# Sheet2.net
KiCad netlist of a schematic drawn in Altium Designer
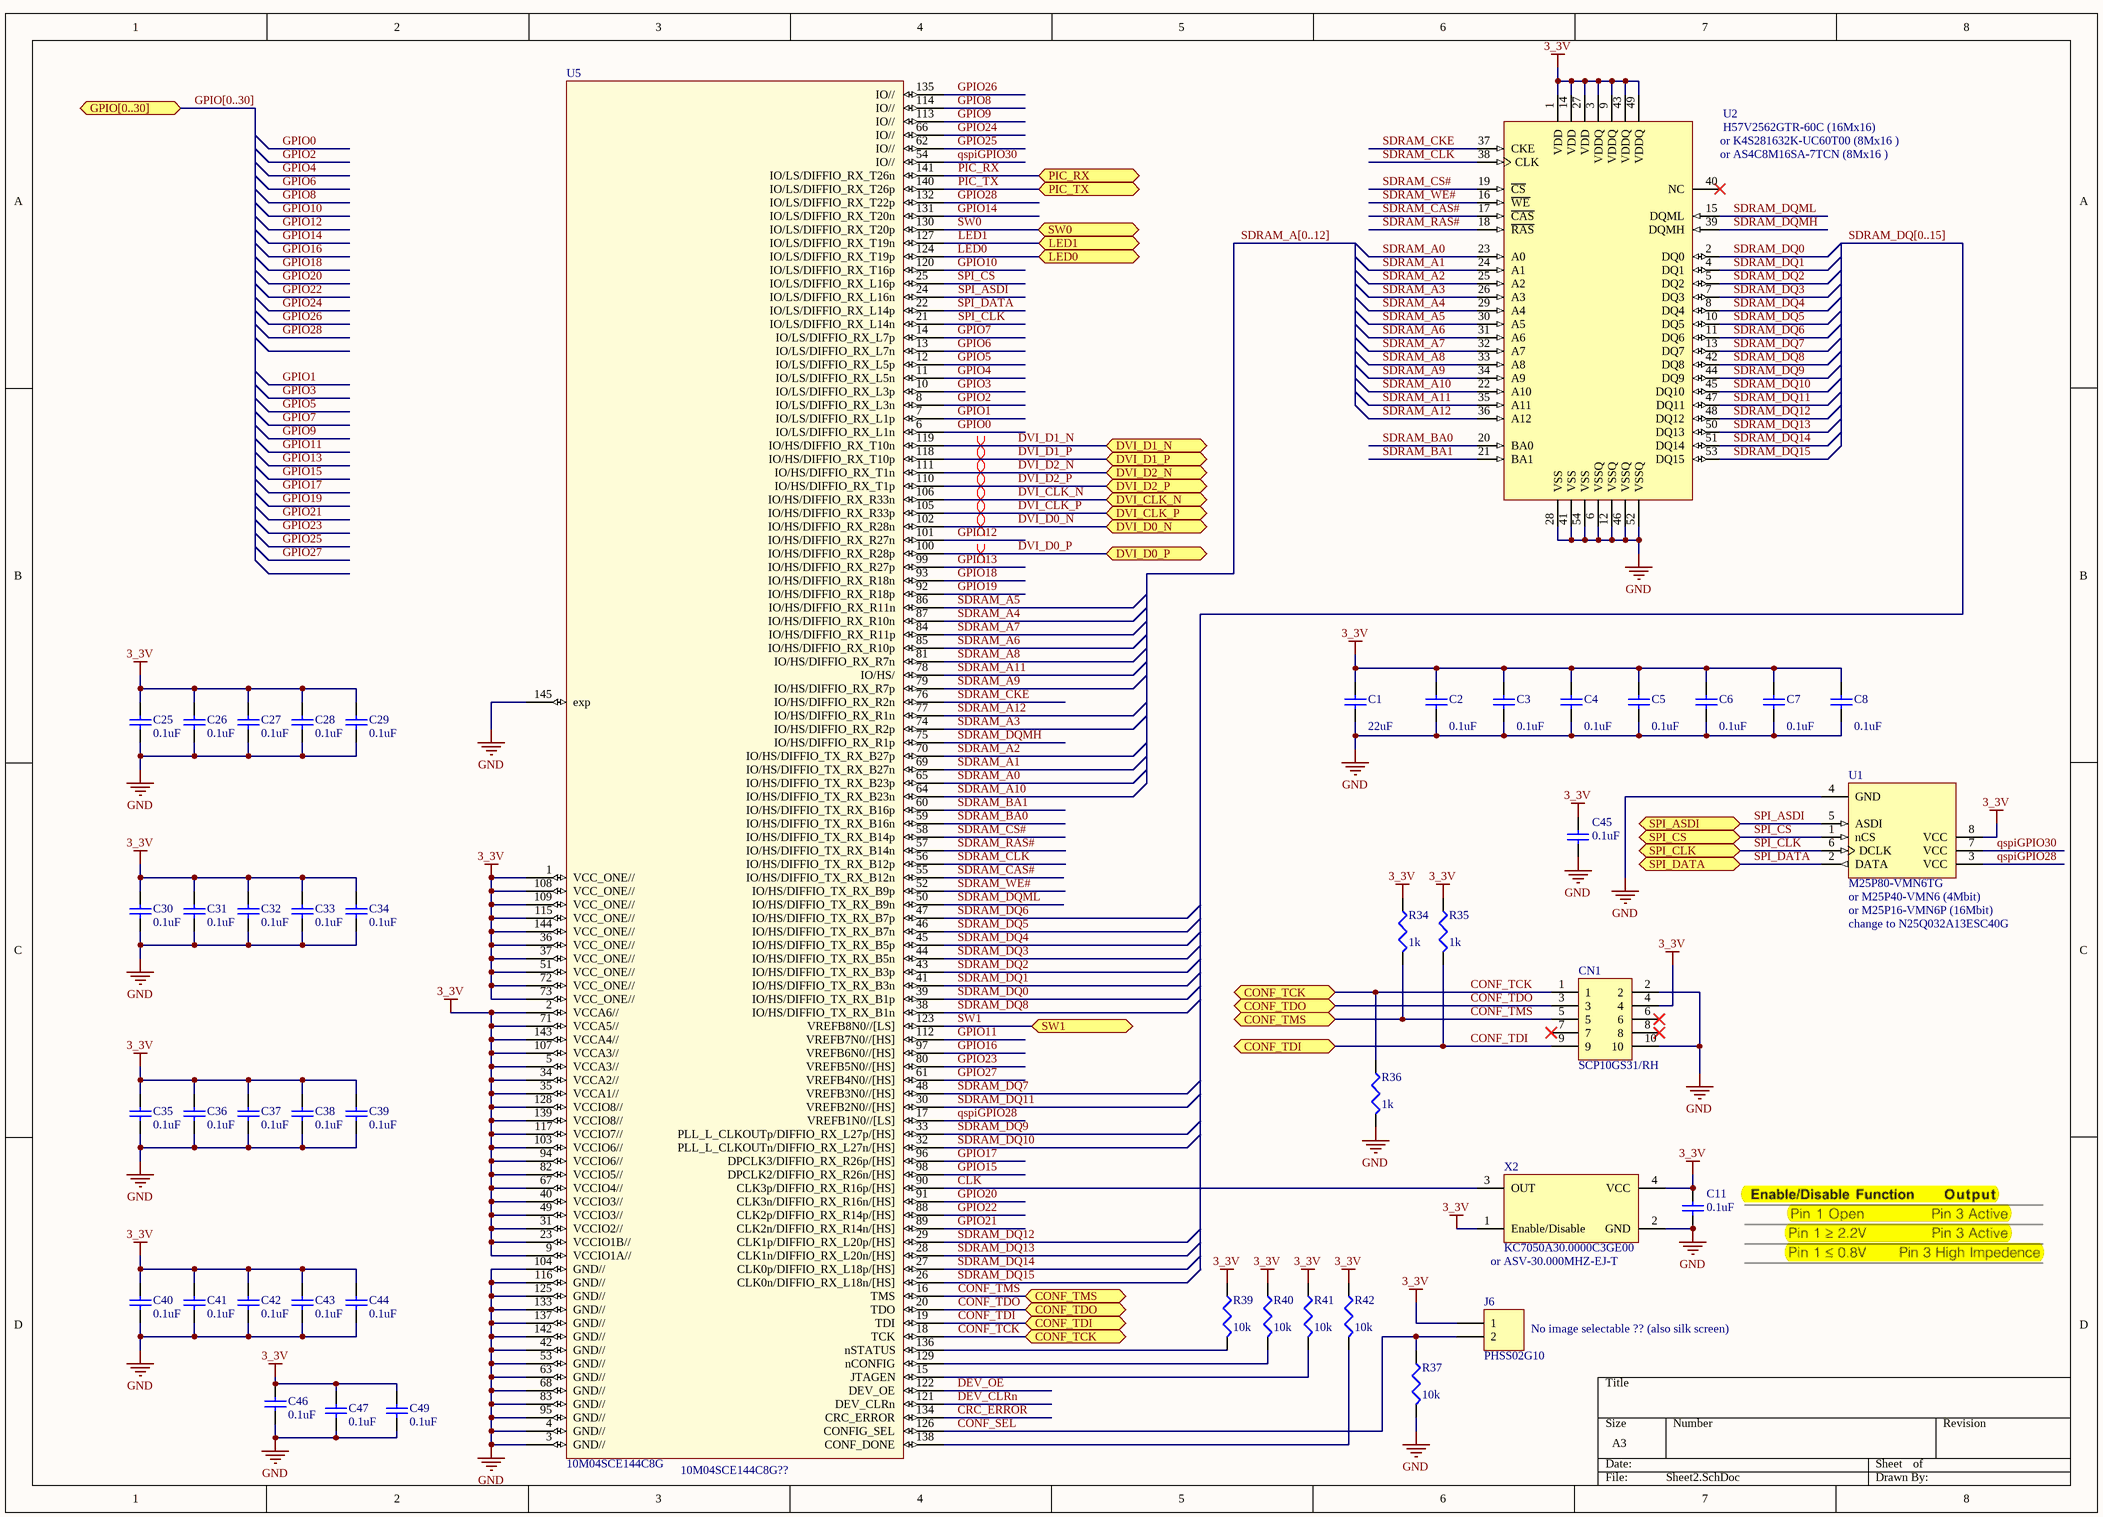
[diagram p0: Sheet2.SchDoc]

(export (version "E")
  (design (tool "Eeschema 10.0.6"))
  (components
    (comp (ref "C1")
      (value "22uF")
      (footprint "PcbLib:CHIP3216")
      (description "Capacitor (Semiconductor SIM Model)")
      (fields (field (name "Comment") "MC1206F226Z100CT") (field (name "PUBLISHER") "Altium Limited"))
      (libsource (lib "Miscellaneous Devices") (part "Cap Semi"))
    )
    (comp (ref "C2")
      (value "0.1uF")
      (footprint "PcbLib:CHIP1608")
      (description "Capacitor (Semiconductor SIM Model)")
      (fields (field (name "Comment") "MC0603B104M160CT") (field (name "PUBLISHER") "Altium Limited"))
      (libsource (lib "Miscellaneous Devices") (part "Cap Semi"))
    )
    (comp (ref "C3")
      (value "0.1uF")
      (footprint "PcbLib:CHIP1608")
      (description "Capacitor (Semiconductor SIM Model)")
      (fields (field (name "Comment") "MC0603B104M160CT") (field (name "PUBLISHER") "Altium Limited"))
      (libsource (lib "Miscellaneous Devices") (part "Cap Semi"))
    )
    (comp (ref "C4")
      (value "0.1uF")
      (footprint "PcbLib:CHIP1608")
      (description "Capacitor (Semiconductor SIM Model)")
      (fields (field (name "Comment") "MC0603B104M160CT") (field (name "PUBLISHER") "Altium Limited"))
      (libsource (lib "Miscellaneous Devices") (part "Cap Semi"))
    )
    (comp (ref "C5")
      (value "0.1uF")
      (footprint "PcbLib:CHIP1608")
      (description "Capacitor (Semiconductor SIM Model)")
      (fields (field (name "Comment") "MC0603B104M160CT") (field (name "PUBLISHER") "Altium Limited"))
      (libsource (lib "Miscellaneous Devices") (part "Cap Semi"))
    )
    (comp (ref "C6")
      (value "0.1uF")
      (footprint "PcbLib:CHIP1608")
      (description "Capacitor (Semiconductor SIM Model)")
      (fields (field (name "Comment") "MC0603B104M160CT") (field (name "PUBLISHER") "Altium Limited"))
      (libsource (lib "Miscellaneous Devices") (part "Cap Semi"))
    )
    (comp (ref "C7")
      (value "0.1uF")
      (footprint "PcbLib:CHIP1608")
      (description "Capacitor (Semiconductor SIM Model)")
      (fields (field (name "Comment") "MC0603B104M160CT") (field (name "PUBLISHER") "Altium Limited"))
      (libsource (lib "Miscellaneous Devices") (part "Cap Semi"))
    )
    (comp (ref "C8")
      (value "0.1uF")
      (footprint "PcbLib:CHIP1608")
      (description "Capacitor (Semiconductor SIM Model)")
      (fields (field (name "Comment") "MC0603B104M160CT") (field (name "PUBLISHER") "Altium Limited"))
      (libsource (lib "Miscellaneous Devices") (part "Cap Semi"))
    )
    (comp (ref "C11")
      (value "0.1uF")
      (footprint "PcbLib:CHIP1608")
      (description "Capacitor (Semiconductor SIM Model)")
      (fields (field (name "Comment") "MC0603B104M160CT") (field (name "PUBLISHER") "Altium Limited"))
      (libsource (lib "Miscellaneous Devices") (part "Cap Semi"))
    )
    (comp (ref "C25")
      (value "0.1uF")
      (footprint "PcbLib:CHIP1608")
      (description "Capacitor (Semiconductor SIM Model)")
      (fields (field (name "Comment") "MC0603B104M160CT") (field (name "PUBLISHER") "Altium Limited"))
      (libsource (lib "Miscellaneous Devices") (part "Cap Semi"))
    )
    (comp (ref "C26")
      (value "0.1uF")
      (footprint "PcbLib:CHIP1608")
      (description "Capacitor (Semiconductor SIM Model)")
      (fields (field (name "Comment") "MC0603B104M160CT") (field (name "PUBLISHER") "Altium Limited"))
      (libsource (lib "Miscellaneous Devices") (part "Cap Semi"))
    )
    (comp (ref "C27")
      (value "0.1uF")
      (footprint "PcbLib:CHIP1608")
      (description "Capacitor (Semiconductor SIM Model)")
      (fields (field (name "Comment") "MC0603B104M160CT") (field (name "PUBLISHER") "Altium Limited"))
      (libsource (lib "Miscellaneous Devices") (part "Cap Semi"))
    )
    (comp (ref "C28")
      (value "0.1uF")
      (footprint "PcbLib:CHIP1608")
      (description "Capacitor (Semiconductor SIM Model)")
      (fields (field (name "Comment") "MC0603B104M160CT") (field (name "PUBLISHER") "Altium Limited"))
      (libsource (lib "Miscellaneous Devices") (part "Cap Semi"))
    )
    (comp (ref "C29")
      (value "0.1uF")
      (footprint "PcbLib:CHIP1608")
      (description "Capacitor (Semiconductor SIM Model)")
      (fields (field (name "Comment") "MC0603B104M160CT") (field (name "PUBLISHER") "Altium Limited"))
      (libsource (lib "Miscellaneous Devices") (part "Cap Semi"))
    )
    (comp (ref "C30")
      (value "0.1uF")
      (footprint "PcbLib:CHIP1608")
      (description "Capacitor (Semiconductor SIM Model)")
      (fields (field (name "Comment") "MC0603B104M160CT") (field (name "PUBLISHER") "Altium Limited"))
      (libsource (lib "Miscellaneous Devices") (part "Cap Semi"))
    )
    (comp (ref "C31")
      (value "0.1uF")
      (footprint "PcbLib:CHIP1608")
      (description "Capacitor (Semiconductor SIM Model)")
      (fields (field (name "Comment") "MC0603B104M160CT") (field (name "PUBLISHER") "Altium Limited"))
      (libsource (lib "Miscellaneous Devices") (part "Cap Semi"))
    )
    (comp (ref "C32")
      (value "0.1uF")
      (footprint "PcbLib:CHIP1608")
      (description "Capacitor (Semiconductor SIM Model)")
      (fields (field (name "Comment") "MC0603B104M160CT") (field (name "PUBLISHER") "Altium Limited"))
      (libsource (lib "Miscellaneous Devices") (part "Cap Semi"))
    )
    (comp (ref "C33")
      (value "0.1uF")
      (footprint "PcbLib:CHIP1608")
      (description "Capacitor (Semiconductor SIM Model)")
      (fields (field (name "Comment") "MC0603B104M160CT") (field (name "PUBLISHER") "Altium Limited"))
      (libsource (lib "Miscellaneous Devices") (part "Cap Semi"))
    )
    (comp (ref "C34")
      (value "0.1uF")
      (footprint "PcbLib:CHIP1608")
      (description "Capacitor (Semiconductor SIM Model)")
      (fields (field (name "Comment") "MC0603B104M160CT") (field (name "PUBLISHER") "Altium Limited"))
      (libsource (lib "Miscellaneous Devices") (part "Cap Semi"))
    )
    (comp (ref "C35")
      (value "0.1uF")
      (footprint "PcbLib:CHIP1608")
      (description "Capacitor (Semiconductor SIM Model)")
      (fields (field (name "Comment") "MC0603B104M160CT") (field (name "PUBLISHER") "Altium Limited"))
      (libsource (lib "Miscellaneous Devices") (part "Cap Semi"))
    )
    (comp (ref "C36")
      (value "0.1uF")
      (footprint "PcbLib:CHIP1608")
      (description "Capacitor (Semiconductor SIM Model)")
      (fields (field (name "Comment") "MC0603B104M160CT") (field (name "PUBLISHER") "Altium Limited"))
      (libsource (lib "Miscellaneous Devices") (part "Cap Semi"))
    )
    (comp (ref "C37")
      (value "0.1uF")
      (footprint "PcbLib:CHIP1608")
      (description "Capacitor (Semiconductor SIM Model)")
      (fields (field (name "Comment") "MC0603B104M160CT") (field (name "PUBLISHER") "Altium Limited"))
      (libsource (lib "Miscellaneous Devices") (part "Cap Semi"))
    )
    (comp (ref "C38")
      (value "0.1uF")
      (footprint "PcbLib:CHIP1608")
      (description "Capacitor (Semiconductor SIM Model)")
      (fields (field (name "Comment") "MC0603B104M160CT") (field (name "PUBLISHER") "Altium Limited"))
      (libsource (lib "Miscellaneous Devices") (part "Cap Semi"))
    )
    (comp (ref "C39")
      (value "0.1uF")
      (footprint "PcbLib:CHIP1608")
      (description "Capacitor (Semiconductor SIM Model)")
      (fields (field (name "Comment") "MC0603B104M160CT") (field (name "PUBLISHER") "Altium Limited"))
      (libsource (lib "Miscellaneous Devices") (part "Cap Semi"))
    )
    (comp (ref "C40")
      (value "0.1uF")
      (footprint "PcbLib:CHIP1608")
      (description "Capacitor (Semiconductor SIM Model)")
      (fields (field (name "Comment") "MC0603B104M160CT") (field (name "PUBLISHER") "Altium Limited"))
      (libsource (lib "Miscellaneous Devices") (part "Cap Semi"))
    )
    (comp (ref "C41")
      (value "0.1uF")
      (footprint "PcbLib:CHIP1608")
      (description "Capacitor (Semiconductor SIM Model)")
      (fields (field (name "Comment") "MC0603B104M160CT") (field (name "PUBLISHER") "Altium Limited"))
      (libsource (lib "Miscellaneous Devices") (part "Cap Semi"))
    )
    (comp (ref "C42")
      (value "0.1uF")
      (footprint "PcbLib:CHIP1608")
      (description "Capacitor (Semiconductor SIM Model)")
      (fields (field (name "Comment") "MC0603B104M160CT") (field (name "PUBLISHER") "Altium Limited"))
      (libsource (lib "Miscellaneous Devices") (part "Cap Semi"))
    )
    (comp (ref "C43")
      (value "0.1uF")
      (footprint "PcbLib:CHIP1608")
      (description "Capacitor (Semiconductor SIM Model)")
      (fields (field (name "Comment") "MC0603B104M160CT") (field (name "PUBLISHER") "Altium Limited"))
      (libsource (lib "Miscellaneous Devices") (part "Cap Semi"))
    )
    (comp (ref "C44")
      (value "0.1uF")
      (footprint "PcbLib:CHIP1608")
      (description "Capacitor (Semiconductor SIM Model)")
      (fields (field (name "Comment") "MC0603B104M160CT") (field (name "PUBLISHER") "Altium Limited"))
      (libsource (lib "Miscellaneous Devices") (part "Cap Semi"))
    )
    (comp (ref "C45")
      (value "0.1uF")
      (footprint "PcbLib:CHIP1608")
      (description "Capacitor (Semiconductor SIM Model)")
      (fields (field (name "Comment") "MC0603B104M160CT") (field (name "PUBLISHER") "Altium Limited"))
      (libsource (lib "Miscellaneous Devices") (part "Cap Semi"))
    )
    (comp (ref "C46")
      (value "0.1uF")
      (footprint "PcbLib:CHIP1608")
      (description "Capacitor (Semiconductor SIM Model)")
      (fields (field (name "Comment") "MC0603B104M160CT") (field (name "PUBLISHER") "Altium Limited"))
      (libsource (lib "Miscellaneous Devices") (part "Cap Semi"))
    )
    (comp (ref "C47")
      (value "0.1uF")
      (footprint "PcbLib:CHIP1608")
      (description "Capacitor (Semiconductor SIM Model)")
      (fields (field (name "Comment") "MC0603B104M160CT") (field (name "PUBLISHER") "Altium Limited"))
      (libsource (lib "Miscellaneous Devices") (part "Cap Semi"))
    )
    (comp (ref "C49")
      (value "0.1uF")
      (footprint "PcbLib:CHIP1608")
      (description "Capacitor (Semiconductor SIM Model)")
      (fields (field (name "Comment") "MC0603B104M160CT") (field (name "PUBLISHER") "Altium Limited"))
      (libsource (lib "Miscellaneous Devices") (part "Cap Semi"))
    )
    (comp (ref "CN1")
      (value "SCP10GS31/RH")
      (footprint "SCP10GS31/RH")
      (description "GTK")
      (libsource (lib "Schlib1") (part "SCP10GS31/RH"))
    )
    (comp (ref "J6")
      (value "PHSS02G10")
      (footprint "PcbLib:HDR1X2")
      (description "Header, 2-Pin")
      (fields (field (name "PUBLISHER") "Altium Limited"))
      (libsource (lib "Miscellaneous Connectors") (part "Header 2"))
    )
    (comp (ref "R34")
      (value "1k")
      (footprint "PcbLib:CHIP1608")
      (description "Resistor")
      (fields (field (name "Comment") "MCMR06X1001FTL") (field (name "PUBLISHER") "Altium Limited"))
      (libsource (lib "Miscellaneous Devices") (part "Res3"))
    )
    (comp (ref "R35")
      (value "1k")
      (footprint "PcbLib:CHIP1608")
      (description "Resistor")
      (fields (field (name "Comment") "MCMR06X1001FTL") (field (name "PUBLISHER") "Altium Limited"))
      (libsource (lib "Miscellaneous Devices") (part "Res3"))
    )
    (comp (ref "R36")
      (value "1k")
      (footprint "PcbLib:CHIP1608")
      (description "Resistor")
      (fields (field (name "Comment") "MCMR06X1001FTL") (field (name "PUBLISHER") "Altium Limited"))
      (libsource (lib "Miscellaneous Devices") (part "Res3"))
    )
    (comp (ref "R37")
      (value "10k")
      (footprint "PcbLib:CHIP1608")
      (description "Resistor")
      (fields (field (name "Comment") "MCWR06X1002FTL") (field (name "PUBLISHER") "Altium Limited"))
      (libsource (lib "Miscellaneous Devices") (part "Res3"))
    )
    (comp (ref "R39")
      (value "10k")
      (footprint "PcbLib:CHIP1608")
      (description "Resistor")
      (fields (field (name "Comment") "MCWR06X1002FTL") (field (name "PUBLISHER") "Altium Limited"))
      (libsource (lib "Miscellaneous Devices") (part "Res3"))
    )
    (comp (ref "R40")
      (value "10k")
      (footprint "PcbLib:CHIP1608")
      (description "Resistor")
      (fields (field (name "Comment") "MCWR06X1002FTL") (field (name "PUBLISHER") "Altium Limited"))
      (libsource (lib "Miscellaneous Devices") (part "Res3"))
    )
    (comp (ref "R41")
      (value "10k")
      (footprint "PcbLib:CHIP1608")
      (description "Resistor")
      (fields (field (name "Comment") "MCWR06X1002FTL") (field (name "PUBLISHER") "Altium Limited"))
      (libsource (lib "Miscellaneous Devices") (part "Res3"))
    )
    (comp (ref "R42")
      (value "10k")
      (footprint "PcbLib:CHIP1608")
      (description "Resistor")
      (fields (field (name "Comment") "MCWR06X1002FTL") (field (name "PUBLISHER") "Altium Limited"))
      (libsource (lib "Miscellaneous Devices") (part "Res3"))
    )
    (comp (ref "U1")
      (value "M25P80-VMN6TG")
      (footprint "PcbLib:SOIC8_L")
      (fields (field (name "PUBLISHER") "Altium Limited"))
      (libsource (lib "Altera EPCS Configuration Device") (part "EPCS1SI8"))
    )
    (comp (ref "U2")
      (value "H57V2562GTR-60C (16Mx16)")
      (footprint "TSOP2-54_M")
      (description "MICRON")
      (fields (field (name "PUBLISHER") "Altium Limited"))
      (libsource (lib "Micron Memory Dynamic RAM") (part "MT48LC16M16A2TG-75"))
    )
    (comp (ref "U5")
      (value "10M04SCE144C8G")
      (footprint "PcbLib:TEST2")
      (description "MAX10")
      (libsource (lib "Schlib") (part "MAX10"))
    )
    (comp (ref "X2")
      (value "KC7050A30.0000C3GE00")
      (footprint "CWX823-50.0M")
      (description "CONNOR-WINFIELD")
      (libsource (lib "Schlib1") (part "CWX823-50.0M"))
    )
  )
  (nets
    (net (code "3") (name "/CLK") (class "Default")
      (node (ref "U5") (pin "90") (pinfunction "CLK3p/DIFFIO_RX_R16p/[HS]_90") (pintype "bidirectional"))
      (node (ref "X2") (pin "3") (pinfunction "OUT_3") (pintype "passive"))
    )
    (net (code "4") (name "/CONF_SEL") (class "Default")
      (node (ref "J6") (pin "2") (pinfunction "2_2") (pintype "passive"))
      (node (ref "R37") (pin "1") (pinfunction "1_1") (pintype "passive"))
      (node (ref "U5") (pin "126") (pinfunction "CONFIG_SEL_126") (pintype "bidirectional"))
    )
    (net (code "5") (name "/CONF_TCK") (class "Default")
      (node (ref "CN1") (pin "1") (pinfunction "1_1") (pintype "passive"))
      (node (ref "R36") (pin "1") (pinfunction "1_1") (pintype "passive"))
      (node (ref "U5") (pin "18") (pinfunction "TCK_18") (pintype "bidirectional"))
    )
    (net (code "6") (name "/CONF_TDI") (class "Default")
      (node (ref "CN1") (pin "9") (pinfunction "9_9") (pintype "passive"))
      (node (ref "R35") (pin "2") (pinfunction "2_2") (pintype "passive"))
      (node (ref "U5") (pin "19") (pinfunction "TDI_19") (pintype "bidirectional"))
    )
    (net (code "7") (name "/CONF_TDO") (class "Default")
      (node (ref "CN1") (pin "3") (pinfunction "3_3") (pintype "passive"))
      (node (ref "U5") (pin "20") (pinfunction "TDO_20") (pintype "bidirectional"))
    )
    (net (code "8") (name "/CONF_TMS") (class "Default")
      (node (ref "CN1") (pin "5") (pinfunction "5_5") (pintype "passive"))
      (node (ref "R34") (pin "2") (pinfunction "2_2") (pintype "passive"))
      (node (ref "U5") (pin "16") (pinfunction "TMS_16") (pintype "bidirectional"))
    )
    (net (code "9") (name "/CRC_ERROR") (class "Default")
      (node (ref "U5") (pin "134") (pinfunction "CRC_ERROR_134") (pintype "bidirectional"))
    )
    (net (code "10") (name "/DEV_CLRn") (class "Default")
      (node (ref "U5") (pin "121") (pinfunction "DEV_CLRn_121") (pintype "bidirectional"))
    )
    (net (code "11") (name "/DEV_OE") (class "Default")
      (node (ref "U5") (pin "122") (pinfunction "DEV_OE_122") (pintype "bidirectional"))
    )
    (net (code "12") (name "/DVI_CLK_N") (class "Default")
      (node (ref "U5") (pin "106") (pinfunction "IO/HS/DIFFIO_RX_R33n_106") (pintype "bidirectional"))
    )
    (net (code "13") (name "/DVI_CLK_P") (class "Default")
      (node (ref "U5") (pin "105") (pinfunction "IO/HS/DIFFIO_RX_R33p_105") (pintype "bidirectional"))
    )
    (net (code "14") (name "/DVI_D0_N") (class "Default")
      (node (ref "U5") (pin "102") (pinfunction "IO/HS/DIFFIO_RX_R28n_102") (pintype "bidirectional"))
    )
    (net (code "15") (name "/DVI_D0_P") (class "Default")
      (node (ref "U5") (pin "100") (pinfunction "IO/HS/DIFFIO_RX_R28p_100") (pintype "bidirectional"))
    )
    (net (code "16") (name "/DVI_D1_N") (class "Default")
      (node (ref "U5") (pin "119") (pinfunction "IO/HS/DIFFIO_RX_T10n_119") (pintype "bidirectional"))
    )
    (net (code "17") (name "/DVI_D1_P") (class "Default")
      (node (ref "U5") (pin "118") (pinfunction "IO/HS/DIFFIO_RX_T10p_118") (pintype "bidirectional"))
    )
    (net (code "18") (name "/DVI_D2_N") (class "Default")
      (node (ref "U5") (pin "111") (pinfunction "IO/HS/DIFFIO_RX_T1n_111") (pintype "bidirectional"))
    )
    (net (code "19") (name "/DVI_D2_P") (class "Default")
      (node (ref "U5") (pin "110") (pinfunction "IO/HS/DIFFIO_RX_T1p_110") (pintype "bidirectional"))
    )
    (net (code "20") (name "/GPIO0") (class "Default")
      (node (ref "U5") (pin "6") (pinfunction "IO/LS/DIFFIO_RX_L1n_6") (pintype "bidirectional"))
    )
    (net (code "21") (name "/GPIO1") (class "Default")
      (node (ref "U5") (pin "7") (pinfunction "IO/LS/DIFFIO_RX_L1p_7") (pintype "bidirectional"))
    )
    (net (code "22") (name "/GPIO2") (class "Default")
      (node (ref "U5") (pin "8") (pinfunction "IO/LS/DIFFIO_RX_L3n_8") (pintype "bidirectional"))
    )
    (net (code "23") (name "/GPIO3") (class "Default")
      (node (ref "U5") (pin "10") (pinfunction "IO/LS/DIFFIO_RX_L3p_10") (pintype "bidirectional"))
    )
    (net (code "24") (name "/GPIO4") (class "Default")
      (node (ref "U5") (pin "11") (pinfunction "IO/LS/DIFFIO_RX_L5n_11") (pintype "bidirectional"))
    )
    (net (code "25") (name "/GPIO5") (class "Default")
      (node (ref "U5") (pin "12") (pinfunction "IO/LS/DIFFIO_RX_L5p_12") (pintype "bidirectional"))
    )
    (net (code "26") (name "/GPIO6") (class "Default")
      (node (ref "U5") (pin "13") (pinfunction "IO/LS/DIFFIO_RX_L7n_13") (pintype "bidirectional"))
    )
    (net (code "27") (name "/GPIO7") (class "Default")
      (node (ref "U5") (pin "14") (pinfunction "IO/LS/DIFFIO_RX_L7p_14") (pintype "bidirectional"))
    )
    (net (code "28") (name "/GPIO8") (class "Default")
      (node (ref "U5") (pin "114") (pinfunction "IO//_114") (pintype "bidirectional"))
    )
    (net (code "29") (name "/GPIO9") (class "Default")
      (node (ref "U5") (pin "113") (pinfunction "IO//_113") (pintype "bidirectional"))
    )
    (net (code "30") (name "/GPIO10") (class "Default")
      (node (ref "U5") (pin "120") (pinfunction "IO/LS/DIFFIO_RX_T16p_120") (pintype "bidirectional"))
    )
    (net (code "31") (name "/GPIO11") (class "Default")
      (node (ref "U5") (pin "112") (pinfunction "VREFB7N0//[HS]_112") (pintype "bidirectional"))
    )
    (net (code "32") (name "/GPIO12") (class "Default")
      (node (ref "U5") (pin "101") (pinfunction "IO/HS/DIFFIO_RX_R27n_101") (pintype "bidirectional"))
    )
    (net (code "33") (name "/GPIO13") (class "Default")
      (node (ref "U5") (pin "99") (pinfunction "IO/HS/DIFFIO_RX_R27p_99") (pintype "bidirectional"))
    )
    (net (code "34") (name "/GPIO14") (class "Default")
      (node (ref "U5") (pin "131") (pinfunction "IO/LS/DIFFIO_RX_T20n_131") (pintype "bidirectional"))
    )
    (net (code "35") (name "/GPIO15") (class "Default")
      (node (ref "U5") (pin "98") (pinfunction "DPCLK2/DIFFIO_RX_R26n/[HS]_98") (pintype "bidirectional"))
    )
    (net (code "36") (name "/GPIO16") (class "Default")
      (node (ref "U5") (pin "97") (pinfunction "VREFB6N0//[HS]_97") (pintype "bidirectional"))
    )
    (net (code "37") (name "/GPIO17") (class "Default")
      (node (ref "U5") (pin "96") (pinfunction "DPCLK3/DIFFIO_RX_R26p/[HS]_96") (pintype "bidirectional"))
    )
    (net (code "38") (name "/GPIO18") (class "Default")
      (node (ref "U5") (pin "93") (pinfunction "IO/HS/DIFFIO_RX_R18n_93") (pintype "bidirectional"))
    )
    (net (code "39") (name "/GPIO19") (class "Default")
      (node (ref "U5") (pin "92") (pinfunction "IO/HS/DIFFIO_RX_R18p_92") (pintype "bidirectional"))
    )
    (net (code "40") (name "/GPIO20") (class "Default")
      (node (ref "U5") (pin "91") (pinfunction "CLK3n/DIFFIO_RX_R16n/[HS]_91") (pintype "bidirectional"))
    )
    (net (code "41") (name "/GPIO21") (class "Default")
      (node (ref "U5") (pin "89") (pinfunction "CLK2n/DIFFIO_RX_R14n/[HS]_89") (pintype "bidirectional"))
    )
    (net (code "42") (name "/GPIO22") (class "Default")
      (node (ref "U5") (pin "88") (pinfunction "CLK2p/DIFFIO_RX_R14p/[HS]_88") (pintype "bidirectional"))
    )
    (net (code "43") (name "/GPIO23") (class "Default")
      (node (ref "U5") (pin "80") (pinfunction "VREFB5N0//[HS]_80") (pintype "bidirectional"))
    )
    (net (code "44") (name "/GPIO24") (class "Default")
      (node (ref "U5") (pin "66") (pinfunction "IO//_66") (pintype "bidirectional"))
    )
    (net (code "45") (name "/GPIO25") (class "Default")
      (node (ref "U5") (pin "62") (pinfunction "IO//_62") (pintype "bidirectional"))
    )
    (net (code "46") (name "/GPIO26") (class "Default")
      (node (ref "U5") (pin "135") (pinfunction "IO//_135") (pintype "bidirectional"))
    )
    (net (code "47") (name "/GPIO27") (class "Default")
      (node (ref "U5") (pin "61") (pinfunction "VREFB4N0//[HS]_61") (pintype "bidirectional"))
    )
    (net (code "48") (name "/GPIO28") (class "Default")
      (node (ref "U5") (pin "132") (pinfunction "IO/LS/DIFFIO_RX_T22p_132") (pintype "bidirectional"))
    )
    (net (code "50") (name "/LED0") (class "Default")
      (node (ref "U5") (pin "124") (pinfunction "IO/LS/DIFFIO_RX_T19p_124") (pintype "bidirectional"))
    )
    (net (code "51") (name "/LED1") (class "Default")
      (node (ref "U5") (pin "127") (pinfunction "IO/LS/DIFFIO_RX_T19n_127") (pintype "bidirectional"))
    )
    (net (code "52") (name "/PIC_RX") (class "Default")
      (node (ref "U5") (pin "141") (pinfunction "IO/LS/DIFFIO_RX_T26n_141") (pintype "bidirectional"))
    )
    (net (code "53") (name "/PIC_TX") (class "Default")
      (node (ref "U5") (pin "140") (pinfunction "IO/LS/DIFFIO_RX_T26p_140") (pintype "bidirectional"))
    )
    (net (code "54") (name "/SDRAM_A0") (class "Default")
      (node (ref "U2") (pin "23") (pinfunction "A0_23") (pintype "input"))
      (node (ref "U5") (pin "65") (pinfunction "IO/HS/DIFFIO_TX_RX_B23p_65") (pintype "bidirectional"))
    )
    (net (code "55") (name "/SDRAM_A1") (class "Default")
      (node (ref "U2") (pin "24") (pinfunction "A1_24") (pintype "input"))
      (node (ref "U5") (pin "69") (pinfunction "IO/HS/DIFFIO_TX_RX_B27n_69") (pintype "bidirectional"))
    )
    (net (code "56") (name "/SDRAM_A2") (class "Default")
      (node (ref "U2") (pin "25") (pinfunction "A2_25") (pintype "input"))
      (node (ref "U5") (pin "70") (pinfunction "IO/HS/DIFFIO_TX_RX_B27p_70") (pintype "bidirectional"))
    )
    (net (code "57") (name "/SDRAM_A3") (class "Default")
      (node (ref "U2") (pin "26") (pinfunction "A3_26") (pintype "input"))
      (node (ref "U5") (pin "74") (pinfunction "IO/HS/DIFFIO_RX_R2p_74") (pintype "bidirectional"))
    )
    (net (code "58") (name "/SDRAM_A4") (class "Default")
      (node (ref "U2") (pin "29") (pinfunction "A4_29") (pintype "input"))
      (node (ref "U5") (pin "87") (pinfunction "IO/HS/DIFFIO_RX_R10n_87") (pintype "bidirectional"))
    )
    (net (code "59") (name "/SDRAM_A5") (class "Default")
      (node (ref "U2") (pin "30") (pinfunction "A5_30") (pintype "input"))
      (node (ref "U5") (pin "86") (pinfunction "IO/HS/DIFFIO_RX_R11n_86") (pintype "bidirectional"))
    )
    (net (code "60") (name "/SDRAM_A6") (class "Default")
      (node (ref "U2") (pin "31") (pinfunction "A6_31") (pintype "input"))
      (node (ref "U5") (pin "85") (pinfunction "IO/HS/DIFFIO_RX_R10p_85") (pintype "bidirectional"))
    )
    (net (code "61") (name "/SDRAM_A7") (class "Default")
      (node (ref "U2") (pin "32") (pinfunction "A7_32") (pintype "input"))
      (node (ref "U5") (pin "84") (pinfunction "IO/HS/DIFFIO_RX_R11p_84") (pintype "bidirectional"))
    )
    (net (code "62") (name "/SDRAM_A8") (class "Default")
      (node (ref "U2") (pin "33") (pinfunction "A8_33") (pintype "input"))
      (node (ref "U5") (pin "81") (pinfunction "IO/HS/DIFFIO_RX_R7n_81") (pintype "bidirectional"))
    )
    (net (code "63") (name "/SDRAM_A9") (class "Default")
      (node (ref "U2") (pin "34") (pinfunction "A9_34") (pintype "input"))
      (node (ref "U5") (pin "79") (pinfunction "IO/HS/DIFFIO_RX_R7p_79") (pintype "bidirectional"))
    )
    (net (code "64") (name "/SDRAM_A10") (class "Default")
      (node (ref "U2") (pin "22") (pinfunction "A10_22") (pintype "input"))
      (node (ref "U5") (pin "64") (pinfunction "IO/HS/DIFFIO_TX_RX_B23n_64") (pintype "bidirectional"))
    )
    (net (code "65") (name "/SDRAM_A11") (class "Default")
      (node (ref "U2") (pin "35") (pinfunction "A11_35") (pintype "input"))
      (node (ref "U5") (pin "78") (pinfunction "IO/HS/_78") (pintype "bidirectional"))
    )
    (net (code "66") (name "/SDRAM_A12") (class "Default")
      (node (ref "U2") (pin "36") (pinfunction "A12_36") (pintype "input"))
      (node (ref "U5") (pin "77") (pinfunction "IO/HS/DIFFIO_RX_R1n_77") (pintype "bidirectional"))
    )
    (net (code "68") (name "/SDRAM_BA0") (class "Default")
      (node (ref "U2") (pin "20") (pinfunction "BA0_20") (pintype "input"))
      (node (ref "U5") (pin "59") (pinfunction "IO/HS/DIFFIO_TX_RX_B16n_59") (pintype "bidirectional"))
    )
    (net (code "69") (name "/SDRAM_BA1") (class "Default")
      (node (ref "U2") (pin "21") (pinfunction "BA1_21") (pintype "input"))
      (node (ref "U5") (pin "60") (pinfunction "IO/HS/DIFFIO_TX_RX_B16p_60") (pintype "bidirectional"))
    )
    (net (code "70") (name "/SDRAM_CAS#") (class "Default")
      (node (ref "U2") (pin "17") (pinfunction "~{CAS}_17") (pintype "input"))
      (node (ref "U5") (pin "55") (pinfunction "IO/HS/DIFFIO_TX_RX_B12n_55") (pintype "bidirectional"))
    )
    (net (code "71") (name "/SDRAM_CKE") (class "Default")
      (node (ref "U2") (pin "37") (pinfunction "CKE_37") (pintype "input"))
      (node (ref "U5") (pin "76") (pinfunction "IO/HS/DIFFIO_RX_R2n_76") (pintype "bidirectional"))
    )
    (net (code "72") (name "/SDRAM_CLK") (class "Default")
      (node (ref "U2") (pin "38") (pinfunction "CLK_38") (pintype "input"))
      (node (ref "U5") (pin "56") (pinfunction "IO/HS/DIFFIO_TX_RX_B12p_56") (pintype "bidirectional"))
    )
    (net (code "73") (name "/SDRAM_CS#") (class "Default")
      (node (ref "U2") (pin "19") (pinfunction "~{CS}_19") (pintype "input"))
      (node (ref "U5") (pin "58") (pinfunction "IO/HS/DIFFIO_TX_RX_B14p_58") (pintype "bidirectional"))
    )
    (net (code "74") (name "/SDRAM_DQ0") (class "Default")
      (node (ref "U2") (pin "2") (pinfunction "DQ0_2") (pintype "bidirectional"))
      (node (ref "U5") (pin "39") (pinfunction "IO/HS/DIFFIO_TX_RX_B1p_39") (pintype "bidirectional"))
    )
    (net (code "75") (name "/SDRAM_DQ1") (class "Default")
      (node (ref "U2") (pin "4") (pinfunction "DQ1_4") (pintype "bidirectional"))
      (node (ref "U5") (pin "41") (pinfunction "IO/HS/DIFFIO_TX_RX_B3n_41") (pintype "bidirectional"))
    )
    (net (code "76") (name "/SDRAM_DQ2") (class "Default")
      (node (ref "U2") (pin "5") (pinfunction "DQ2_5") (pintype "bidirectional"))
      (node (ref "U5") (pin "43") (pinfunction "IO/HS/DIFFIO_TX_RX_B3p_43") (pintype "bidirectional"))
    )
    (net (code "77") (name "/SDRAM_DQ3") (class "Default")
      (node (ref "U2") (pin "7") (pinfunction "DQ3_7") (pintype "bidirectional"))
      (node (ref "U5") (pin "44") (pinfunction "IO/HS/DIFFIO_TX_RX_B5n_44") (pintype "bidirectional"))
    )
    (net (code "78") (name "/SDRAM_DQ4") (class "Default")
      (node (ref "U2") (pin "8") (pinfunction "DQ4_8") (pintype "bidirectional"))
      (node (ref "U5") (pin "45") (pinfunction "IO/HS/DIFFIO_TX_RX_B5p_45") (pintype "bidirectional"))
    )
    (net (code "79") (name "/SDRAM_DQ5") (class "Default")
      (node (ref "U2") (pin "10") (pinfunction "DQ5_10") (pintype "bidirectional"))
      (node (ref "U5") (pin "46") (pinfunction "IO/HS/DIFFIO_TX_RX_B7n_46") (pintype "bidirectional"))
    )
    (net (code "80") (name "/SDRAM_DQ6") (class "Default")
      (node (ref "U2") (pin "11") (pinfunction "DQ6_11") (pintype "bidirectional"))
      (node (ref "U5") (pin "47") (pinfunction "IO/HS/DIFFIO_TX_RX_B7p_47") (pintype "bidirectional"))
    )
    (net (code "81") (name "/SDRAM_DQ7") (class "Default")
      (node (ref "U2") (pin "13") (pinfunction "DQ7_13") (pintype "bidirectional"))
      (node (ref "U5") (pin "48") (pinfunction "VREFB3N0//[HS]_48") (pintype "bidirectional"))
    )
    (net (code "82") (name "/SDRAM_DQ8") (class "Default")
      (node (ref "U2") (pin "42") (pinfunction "DQ8_42") (pintype "bidirectional"))
      (node (ref "U5") (pin "38") (pinfunction "IO/HS/DIFFIO_TX_RX_B1n_38") (pintype "bidirectional"))
    )
    (net (code "83") (name "/SDRAM_DQ9") (class "Default")
      (node (ref "U2") (pin "44") (pinfunction "DQ9_44") (pintype "bidirectional"))
      (node (ref "U5") (pin "33") (pinfunction "PLL_L_CLKOUTp/DIFFIO_RX_L27p/[HS]_33") (pintype "bidirectional"))
    )
    (net (code "84") (name "/SDRAM_DQ10") (class "Default")
      (node (ref "U2") (pin "45") (pinfunction "DQ10_45") (pintype "bidirectional"))
      (node (ref "U5") (pin "32") (pinfunction "PLL_L_CLKOUTn/DIFFIO_RX_L27n/[HS]_32") (pintype "bidirectional"))
    )
    (net (code "85") (name "/SDRAM_DQ11") (class "Default")
      (node (ref "U2") (pin "47") (pinfunction "DQ11_47") (pintype "bidirectional"))
      (node (ref "U5") (pin "30") (pinfunction "VREFB2N0//[HS]_30") (pintype "bidirectional"))
    )
    (net (code "86") (name "/SDRAM_DQ12") (class "Default")
      (node (ref "U2") (pin "48") (pinfunction "DQ12_48") (pintype "bidirectional"))
      (node (ref "U5") (pin "29") (pinfunction "CLK1p/DIFFIO_RX_L20p/[HS]_29") (pintype "bidirectional"))
    )
    (net (code "87") (name "/SDRAM_DQ13") (class "Default")
      (node (ref "U2") (pin "50") (pinfunction "DQ13_50") (pintype "bidirectional"))
      (node (ref "U5") (pin "28") (pinfunction "CLK1n/DIFFIO_RX_L20n/[HS]_28") (pintype "bidirectional"))
    )
    (net (code "88") (name "/SDRAM_DQ14") (class "Default")
      (node (ref "U2") (pin "51") (pinfunction "DQ14_51") (pintype "bidirectional"))
      (node (ref "U5") (pin "27") (pinfunction "CLK0p/DIFFIO_RX_L18p/[HS]_27") (pintype "bidirectional"))
    )
    (net (code "89") (name "/SDRAM_DQ15") (class "Default")
      (node (ref "U2") (pin "53") (pinfunction "DQ15_53") (pintype "bidirectional"))
      (node (ref "U5") (pin "26") (pinfunction "CLK0n/DIFFIO_RX_L18n/[HS]_26") (pintype "bidirectional"))
    )
    (net (code "90") (name "/SDRAM_DQMH") (class "Default")
      (node (ref "U2") (pin "39") (pinfunction "DQMH_39") (pintype "input"))
      (node (ref "U5") (pin "75") (pinfunction "IO/HS/DIFFIO_RX_R1p_75") (pintype "bidirectional"))
    )
    (net (code "91") (name "/SDRAM_DQML") (class "Default")
      (node (ref "U2") (pin "15") (pinfunction "DQML_15") (pintype "input"))
      (node (ref "U5") (pin "50") (pinfunction "IO/HS/DIFFIO_TX_RX_B9n_50") (pintype "bidirectional"))
    )
    (net (code "93") (name "/SDRAM_RAS#") (class "Default")
      (node (ref "U2") (pin "18") (pinfunction "~{RAS}_18") (pintype "input"))
      (node (ref "U5") (pin "57") (pinfunction "IO/HS/DIFFIO_TX_RX_B14n_57") (pintype "bidirectional"))
    )
    (net (code "94") (name "/SDRAM_WE#") (class "Default")
      (node (ref "U2") (pin "16") (pinfunction "~{WE}_16") (pintype "input"))
      (node (ref "U5") (pin "52") (pinfunction "IO/HS/DIFFIO_TX_RX_B9p_52") (pintype "bidirectional"))
    )
    (net (code "95") (name "/SPI_ASDI") (class "Default")
      (node (ref "U1") (pin "5") (pinfunction "ASDI_5") (pintype "input"))
      (node (ref "U5") (pin "24") (pinfunction "IO/LS/DIFFIO_RX_L16n_24") (pintype "bidirectional"))
    )
    (net (code "96") (name "/SPI_CLK") (class "Default")
      (node (ref "U1") (pin "6") (pinfunction "DCLK_6") (pintype "input"))
      (node (ref "U5") (pin "21") (pinfunction "IO/LS/DIFFIO_RX_L14n_21") (pintype "bidirectional"))
    )
    (net (code "97") (name "/SPI_CS") (class "Default")
      (node (ref "U1") (pin "1") (pinfunction "nCS_1") (pintype "input"))
      (node (ref "U5") (pin "25") (pinfunction "IO/LS/DIFFIO_RX_L16p_25") (pintype "bidirectional"))
    )
    (net (code "98") (name "/SPI_DATA") (class "Default")
      (node (ref "U1") (pin "2") (pinfunction "DATA_2") (pintype "output"))
      (node (ref "U5") (pin "22") (pinfunction "IO/LS/DIFFIO_RX_L14p_22") (pintype "bidirectional"))
    )
    (net (code "99") (name "/SW0") (class "Default")
      (node (ref "U5") (pin "130") (pinfunction "IO/LS/DIFFIO_RX_T20p_130") (pintype "bidirectional"))
    )
    (net (code "100") (name "/SW1") (class "Default")
      (node (ref "U5") (pin "123") (pinfunction "VREFB8N0//[LS]_123") (pintype "bidirectional"))
    )
    (net (code "101") (name "/qspiGPIO28") (class "Default")
      (node (ref "U1") (pin "3") (pinfunction "VCC_3") (pintype "power_in"))
      (node (ref "U5") (pin "17") (pinfunction "VREFB1N0//[LS]_17") (pintype "bidirectional"))
    )
    (net (code "102") (name "/qspiGPIO30") (class "Default")
      (node (ref "U1") (pin "7") (pinfunction "VCC_7") (pintype "power_in"))
      (node (ref "U5") (pin "54") (pinfunction "IO//_54") (pintype "bidirectional"))
    )
    (net (code "103") (name "3_3V") (class "Default")
      (node (ref "C1") (pin "2") (pinfunction "2_2") (pintype "passive"))
      (node (ref "C11") (pin "2") (pinfunction "2_2") (pintype "passive"))
      (node (ref "C2") (pin "2") (pinfunction "2_2") (pintype "passive"))
      (node (ref "C25") (pin "1") (pinfunction "1_1") (pintype "passive"))
      (node (ref "C26") (pin "1") (pinfunction "1_1") (pintype "passive"))
      (node (ref "C27") (pin "1") (pinfunction "1_1") (pintype "passive"))
      (node (ref "C28") (pin "1") (pinfunction "1_1") (pintype "passive"))
      (node (ref "C29") (pin "1") (pinfunction "1_1") (pintype "passive"))
      (node (ref "C3") (pin "2") (pinfunction "2_2") (pintype "passive"))
      (node (ref "C30") (pin "1") (pinfunction "1_1") (pintype "passive"))
      (node (ref "C31") (pin "1") (pinfunction "1_1") (pintype "passive"))
      (node (ref "C32") (pin "1") (pinfunction "1_1") (pintype "passive"))
      (node (ref "C33") (pin "1") (pinfunction "1_1") (pintype "passive"))
      (node (ref "C34") (pin "1") (pinfunction "1_1") (pintype "passive"))
      (node (ref "C35") (pin "1") (pinfunction "1_1") (pintype "passive"))
      (node (ref "C36") (pin "1") (pinfunction "1_1") (pintype "passive"))
      (node (ref "C37") (pin "1") (pinfunction "1_1") (pintype "passive"))
      (node (ref "C38") (pin "1") (pinfunction "1_1") (pintype "passive"))
      (node (ref "C39") (pin "1") (pinfunction "1_1") (pintype "passive"))
      (node (ref "C4") (pin "2") (pinfunction "2_2") (pintype "passive"))
      (node (ref "C40") (pin "1") (pinfunction "1_1") (pintype "passive"))
      (node (ref "C41") (pin "1") (pinfunction "1_1") (pintype "passive"))
      (node (ref "C42") (pin "1") (pinfunction "1_1") (pintype "passive"))
      (node (ref "C43") (pin "1") (pinfunction "1_1") (pintype "passive"))
      (node (ref "C44") (pin "1") (pinfunction "1_1") (pintype "passive"))
      (node (ref "C45") (pin "2") (pinfunction "2_2") (pintype "passive"))
      (node (ref "C46") (pin "1") (pinfunction "1_1") (pintype "passive"))
      (node (ref "C47") (pin "1") (pinfunction "1_1") (pintype "passive"))
      (node (ref "C49") (pin "1") (pinfunction "1_1") (pintype "passive"))
      (node (ref "C5") (pin "2") (pinfunction "2_2") (pintype "passive"))
      (node (ref "C6") (pin "2") (pinfunction "2_2") (pintype "passive"))
      (node (ref "C7") (pin "2") (pinfunction "2_2") (pintype "passive"))
      (node (ref "C8") (pin "2") (pinfunction "2_2") (pintype "passive"))
      (node (ref "CN1") (pin "4") (pinfunction "4_4") (pintype "passive"))
      (node (ref "J6") (pin "1") (pinfunction "1_1") (pintype "passive"))
      (node (ref "R34") (pin "1") (pinfunction "1_1") (pintype "passive"))
      (node (ref "R35") (pin "1") (pinfunction "1_1") (pintype "passive"))
      (node (ref "R39") (pin "1") (pinfunction "1_1") (pintype "passive"))
      (node (ref "R40") (pin "1") (pinfunction "1_1") (pintype "passive"))
      (node (ref "R41") (pin "1") (pinfunction "1_1") (pintype "passive"))
      (node (ref "R42") (pin "1") (pinfunction "1_1") (pintype "passive"))
      (node (ref "U1") (pin "8") (pinfunction "VCC_8") (pintype "power_in"))
      (node (ref "U2") (pin "1") (pinfunction "VDD_1") (pintype "power_in"))
      (node (ref "U2") (pin "14") (pinfunction "VDD_14") (pintype "power_in"))
      (node (ref "U2") (pin "27") (pinfunction "VDD_27") (pintype "power_in"))
      (node (ref "U2") (pin "3") (pinfunction "VDDQ_3") (pintype "power_in"))
      (node (ref "U2") (pin "43") (pinfunction "VDDQ_43") (pintype "power_in"))
      (node (ref "U2") (pin "49") (pinfunction "VDDQ_49") (pintype "power_in"))
      (node (ref "U2") (pin "9") (pinfunction "VDDQ_9") (pintype "power_in"))
      (node (ref "U5") (pin "1") (pinfunction "VCC_ONE//_1") (pintype "bidirectional"))
      (node (ref "U5") (pin "103") (pinfunction "VCCIO6//_103") (pintype "bidirectional"))
      (node (ref "U5") (pin "107") (pinfunction "VCCA3//_107") (pintype "bidirectional"))
      (node (ref "U5") (pin "108") (pinfunction "VCC_ONE//_108") (pintype "bidirectional"))
      (node (ref "U5") (pin "109") (pinfunction "VCC_ONE//_109") (pintype "bidirectional"))
      (node (ref "U5") (pin "115") (pinfunction "VCC_ONE//_115") (pintype "bidirectional"))
      (node (ref "U5") (pin "117") (pinfunction "VCCIO7//_117") (pintype "bidirectional"))
      (node (ref "U5") (pin "128") (pinfunction "VCCIO8//_128") (pintype "bidirectional"))
      (node (ref "U5") (pin "139") (pinfunction "VCCIO8//_139") (pintype "bidirectional"))
      (node (ref "U5") (pin "143") (pinfunction "VCCA4//_143") (pintype "bidirectional"))
      (node (ref "U5") (pin "144") (pinfunction "VCC_ONE//_144") (pintype "bidirectional"))
      (node (ref "U5") (pin "2") (pinfunction "VCCA6//_2") (pintype "bidirectional"))
      (node (ref "U5") (pin "23") (pinfunction "VCCIO1B//_23") (pintype "bidirectional"))
      (node (ref "U5") (pin "31") (pinfunction "VCCIO2//_31") (pintype "bidirectional"))
      (node (ref "U5") (pin "34") (pinfunction "VCCA2//_34") (pintype "bidirectional"))
      (node (ref "U5") (pin "35") (pinfunction "VCCA1//_35") (pintype "bidirectional"))
      (node (ref "U5") (pin "36") (pinfunction "VCC_ONE//_36") (pintype "bidirectional"))
      (node (ref "U5") (pin "37") (pinfunction "VCC_ONE//_37") (pintype "bidirectional"))
      (node (ref "U5") (pin "40") (pinfunction "VCCIO3//_40") (pintype "bidirectional"))
      (node (ref "U5") (pin "49") (pinfunction "VCCIO3//_49") (pintype "bidirectional"))
      (node (ref "U5") (pin "5") (pinfunction "VCCA3//_5") (pintype "bidirectional"))
      (node (ref "U5") (pin "51") (pinfunction "VCC_ONE//_51") (pintype "bidirectional"))
      (node (ref "U5") (pin "67") (pinfunction "VCCIO4//_67") (pintype "bidirectional"))
      (node (ref "U5") (pin "71") (pinfunction "VCCA5//_71") (pintype "bidirectional"))
      (node (ref "U5") (pin "72") (pinfunction "VCC_ONE//_72") (pintype "bidirectional"))
      (node (ref "U5") (pin "73") (pinfunction "VCC_ONE//_73") (pintype "bidirectional"))
      (node (ref "U5") (pin "82") (pinfunction "VCCIO5//_82") (pintype "bidirectional"))
      (node (ref "U5") (pin "9") (pinfunction "VCCIO1A//_9") (pintype "bidirectional"))
      (node (ref "U5") (pin "94") (pinfunction "VCCIO6//_94") (pintype "bidirectional"))
      (node (ref "X2") (pin "1") (pinfunction "Enable/Disable_1") (pintype "passive"))
      (node (ref "X2") (pin "4") (pinfunction "VCC_4") (pintype "passive"))
    )
    (net (code "104") (name "GND") (class "Default")
      (node (ref "C1") (pin "1") (pinfunction "1_1") (pintype "passive"))
      (node (ref "C11") (pin "1") (pinfunction "1_1") (pintype "passive"))
      (node (ref "C2") (pin "1") (pinfunction "1_1") (pintype "passive"))
      (node (ref "C25") (pin "2") (pinfunction "2_2") (pintype "passive"))
      (node (ref "C26") (pin "2") (pinfunction "2_2") (pintype "passive"))
      (node (ref "C27") (pin "2") (pinfunction "2_2") (pintype "passive"))
      (node (ref "C28") (pin "2") (pinfunction "2_2") (pintype "passive"))
      (node (ref "C29") (pin "2") (pinfunction "2_2") (pintype "passive"))
      (node (ref "C3") (pin "1") (pinfunction "1_1") (pintype "passive"))
      (node (ref "C30") (pin "2") (pinfunction "2_2") (pintype "passive"))
      (node (ref "C31") (pin "2") (pinfunction "2_2") (pintype "passive"))
      (node (ref "C32") (pin "2") (pinfunction "2_2") (pintype "passive"))
      (node (ref "C33") (pin "2") (pinfunction "2_2") (pintype "passive"))
      (node (ref "C34") (pin "2") (pinfunction "2_2") (pintype "passive"))
      (node (ref "C35") (pin "2") (pinfunction "2_2") (pintype "passive"))
      (node (ref "C36") (pin "2") (pinfunction "2_2") (pintype "passive"))
      (node (ref "C37") (pin "2") (pinfunction "2_2") (pintype "passive"))
      (node (ref "C38") (pin "2") (pinfunction "2_2") (pintype "passive"))
      (node (ref "C39") (pin "2") (pinfunction "2_2") (pintype "passive"))
      (node (ref "C4") (pin "1") (pinfunction "1_1") (pintype "passive"))
      (node (ref "C40") (pin "2") (pinfunction "2_2") (pintype "passive"))
      (node (ref "C41") (pin "2") (pinfunction "2_2") (pintype "passive"))
      (node (ref "C42") (pin "2") (pinfunction "2_2") (pintype "passive"))
      (node (ref "C43") (pin "2") (pinfunction "2_2") (pintype "passive"))
      (node (ref "C44") (pin "2") (pinfunction "2_2") (pintype "passive"))
      (node (ref "C45") (pin "1") (pinfunction "1_1") (pintype "passive"))
      (node (ref "C46") (pin "2") (pinfunction "2_2") (pintype "passive"))
      (node (ref "C47") (pin "2") (pinfunction "2_2") (pintype "passive"))
      (node (ref "C49") (pin "2") (pinfunction "2_2") (pintype "passive"))
      (node (ref "C5") (pin "1") (pinfunction "1_1") (pintype "passive"))
      (node (ref "C6") (pin "1") (pinfunction "1_1") (pintype "passive"))
      (node (ref "C7") (pin "1") (pinfunction "1_1") (pintype "passive"))
      (node (ref "C8") (pin "1") (pinfunction "1_1") (pintype "passive"))
      (node (ref "CN1") (pin "10") (pinfunction "10_10") (pintype "passive"))
      (node (ref "CN1") (pin "2") (pinfunction "2_2") (pintype "passive"))
      (node (ref "R36") (pin "2") (pinfunction "2_2") (pintype "passive"))
      (node (ref "R37") (pin "2") (pinfunction "2_2") (pintype "passive"))
      (node (ref "U1") (pin "4") (pinfunction "GND_4") (pintype "power_in"))
      (node (ref "U2") (pin "12") (pinfunction "VSSQ_12") (pintype "power_in"))
      (node (ref "U2") (pin "28") (pinfunction "VSS_28") (pintype "power_in"))
      (node (ref "U2") (pin "41") (pinfunction "VSS_41") (pintype "power_in"))
      (node (ref "U2") (pin "46") (pinfunction "VSSQ_46") (pintype "power_in"))
      (node (ref "U2") (pin "52") (pinfunction "VSSQ_52") (pintype "power_in"))
      (node (ref "U2") (pin "54") (pinfunction "VSS_54") (pintype "power_in"))
      (node (ref "U2") (pin "6") (pinfunction "VSSQ_6") (pintype "power_in"))
      (node (ref "U5") (pin "104") (pinfunction "GND//_104") (pintype "bidirectional"))
      (node (ref "U5") (pin "116") (pinfunction "GND//_116") (pintype "bidirectional"))
      (node (ref "U5") (pin "125") (pinfunction "GND//_125") (pintype "bidirectional"))
      (node (ref "U5") (pin "133") (pinfunction "GND//_133") (pintype "bidirectional"))
      (node (ref "U5") (pin "137") (pinfunction "GND//_137") (pintype "bidirectional"))
      (node (ref "U5") (pin "142") (pinfunction "GND//_142") (pintype "bidirectional"))
      (node (ref "U5") (pin "145") (pinfunction "exp_145") (pintype "bidirectional"))
      (node (ref "U5") (pin "3") (pinfunction "GND//_3") (pintype "bidirectional"))
      (node (ref "U5") (pin "4") (pinfunction "GND//_4") (pintype "bidirectional"))
      (node (ref "U5") (pin "42") (pinfunction "GND//_42") (pintype "bidirectional"))
      (node (ref "U5") (pin "53") (pinfunction "GND//_53") (pintype "bidirectional"))
      (node (ref "U5") (pin "63") (pinfunction "GND//_63") (pintype "bidirectional"))
      (node (ref "U5") (pin "68") (pinfunction "GND//_68") (pintype "bidirectional"))
      (node (ref "U5") (pin "83") (pinfunction "GND//_83") (pintype "bidirectional"))
      (node (ref "U5") (pin "95") (pinfunction "GND//_95") (pintype "bidirectional"))
      (node (ref "X2") (pin "2") (pinfunction "GND_2") (pintype "passive"))
    )
    (net (code "105") (name "Net-(U5-CONF_DONE)") (class "Default")
      (node (ref "R42") (pin "2") (pinfunction "2_2") (pintype "passive"))
      (node (ref "U5") (pin "138") (pinfunction "CONF_DONE_138") (pintype "bidirectional"))
    )
    (net (code "106") (name "Net-(U5-JTAGEN)") (class "Default")
      (node (ref "R41") (pin "2") (pinfunction "2_2") (pintype "passive"))
      (node (ref "U5") (pin "15") (pinfunction "JTAGEN_15") (pintype "bidirectional"))
    )
    (net (code "107") (name "Net-(U5-nCONFIG)") (class "Default")
      (node (ref "R40") (pin "2") (pinfunction "2_2") (pintype "passive"))
      (node (ref "U5") (pin "129") (pinfunction "nCONFIG_129") (pintype "bidirectional"))
    )
    (net (code "108") (name "Net-(U5-nSTATUS)") (class "Default")
      (node (ref "R39") (pin "2") (pinfunction "2_2") (pintype "passive"))
      (node (ref "U5") (pin "136") (pinfunction "nSTATUS_136") (pintype "bidirectional"))
    )
    (net (code "109") (name "unconnected-(CN1-Pad6)") (class "Default")
      (node (ref "CN1") (pin "6") (pinfunction "6_6") (pintype "passive+no_connect"))
    )
    (net (code "110") (name "unconnected-(CN1-Pad7)") (class "Default")
      (node (ref "CN1") (pin "7") (pinfunction "7_7") (pintype "passive+no_connect"))
    )
    (net (code "111") (name "unconnected-(CN1-Pad8)") (class "Default")
      (node (ref "CN1") (pin "8") (pinfunction "8_8") (pintype "passive+no_connect"))
    )
    (net (code "112") (name "unconnected-(U2-NC-Pad40)") (class "Default")
      (node (ref "U2") (pin "40") (pinfunction "NC_40") (pintype "passive+no_connect"))
    )
  )
)
